# incomplete.net
KiCad netlist of a schematic drawn in EAGLE
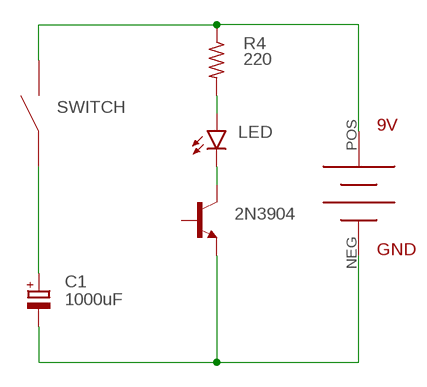
[diagram p0: schematic, sheet 1]

(export (version "E")
  (design (tool "Eeschema 10.0.6"))
  (components
    (comp (ref "C1")
      (value "1000uF")
      (footprint "eagle-import:B45181B")
      (libsource (lib "eagle-import") (part "CPOL-EUB45181B"))
    )
    (comp (ref "LED")
      (value "LED5MM")
      (footprint "eagle-import:LED5MM")
      (libsource (lib "eagle-import") (part "LED5MM"))
    )
    (comp (ref "R4")
      (value "220")
      (footprint "eagle-import:0207_10")
      (libsource (lib "eagle-import") (part "R-US_0207/10"))
    )
    (comp (ref "T3")
      (value "2N3904")
      (footprint "eagle-import:TO92")
      (libsource (lib "eagle-import") (part "2N3904"))
    )
    (comp (ref "U$1")
      (value "PWR_DEMO")
      (footprint "eagle-import:PWR_DEMO")
      (libsource (lib "eagle-import") (part "PWR_DEMO"))
    )
    (comp (ref "U$2")
      (value "TACT_SWITCH_6MM")
      (footprint "eagle-import:TACT_SWITCH_6MM")
      (libsource (lib "eagle-import") (part "TACT_SWITCH_6MM"))
    )
  )
  (nets
    (net (code "1") (name "Net-(C1-Pad+)") (class "Default")
      (node (ref "C1") (pin "+") (pinfunction "+_+") (pintype "passive"))
      (node (ref "U$2") (pin "A1") (pinfunction "A_A1") (pintype "bidirectional"))
      (node (ref "U$2") (pin "A2") (pinfunction "A_A2") (pintype "bidirectional"))
    )
    (net (code "2") (name "Net-(LED-C)") (class "Default")
      (node (ref "LED") (pin "K") (pinfunction "C_K") (pintype "passive"))
      (node (ref "T3") (pin "1") (pinfunction "C_1") (pintype "passive"))
    )
    (net (code "3") (name "Net-(LED-PadA)") (class "Default")
      (node (ref "LED") (pin "A") (pinfunction "A_A") (pintype "passive"))
      (node (ref "R4") (pin "2") (pinfunction "2_2") (pintype "passive"))
    )
    (net (code "4") (name "Net-(R4-Pad1)") (class "Default")
      (node (ref "R4") (pin "1") (pinfunction "1_1") (pintype "passive"))
      (node (ref "U$1") (pin "POS") (pinfunction "POS_POS") (pintype "bidirectional"))
      (node (ref "U$2") (pin "B1") (pinfunction "B_B1") (pintype "bidirectional"))
      (node (ref "U$2") (pin "B2") (pinfunction "B_B2") (pintype "bidirectional"))
    )
    (net (code "5") (name "Net-(T3-E)") (class "Default")
      (node (ref "C1") (pin "-") (pinfunction "-_-") (pintype "passive"))
      (node (ref "T3") (pin "3") (pinfunction "E_3") (pintype "passive"))
      (node (ref "U$1") (pin "NEG") (pinfunction "NEG_NEG") (pintype "bidirectional"))
    )
    (net (code "6") (name "unconnected-(T3-B-Pad2)") (class "Default")
      (node (ref "T3") (pin "2") (pinfunction "B_2") (pintype "passive"))
    )
  )
)
